# SW6124_A_B_C_LED.net
KiCad netlist of a schematic drawn in Altium Designer
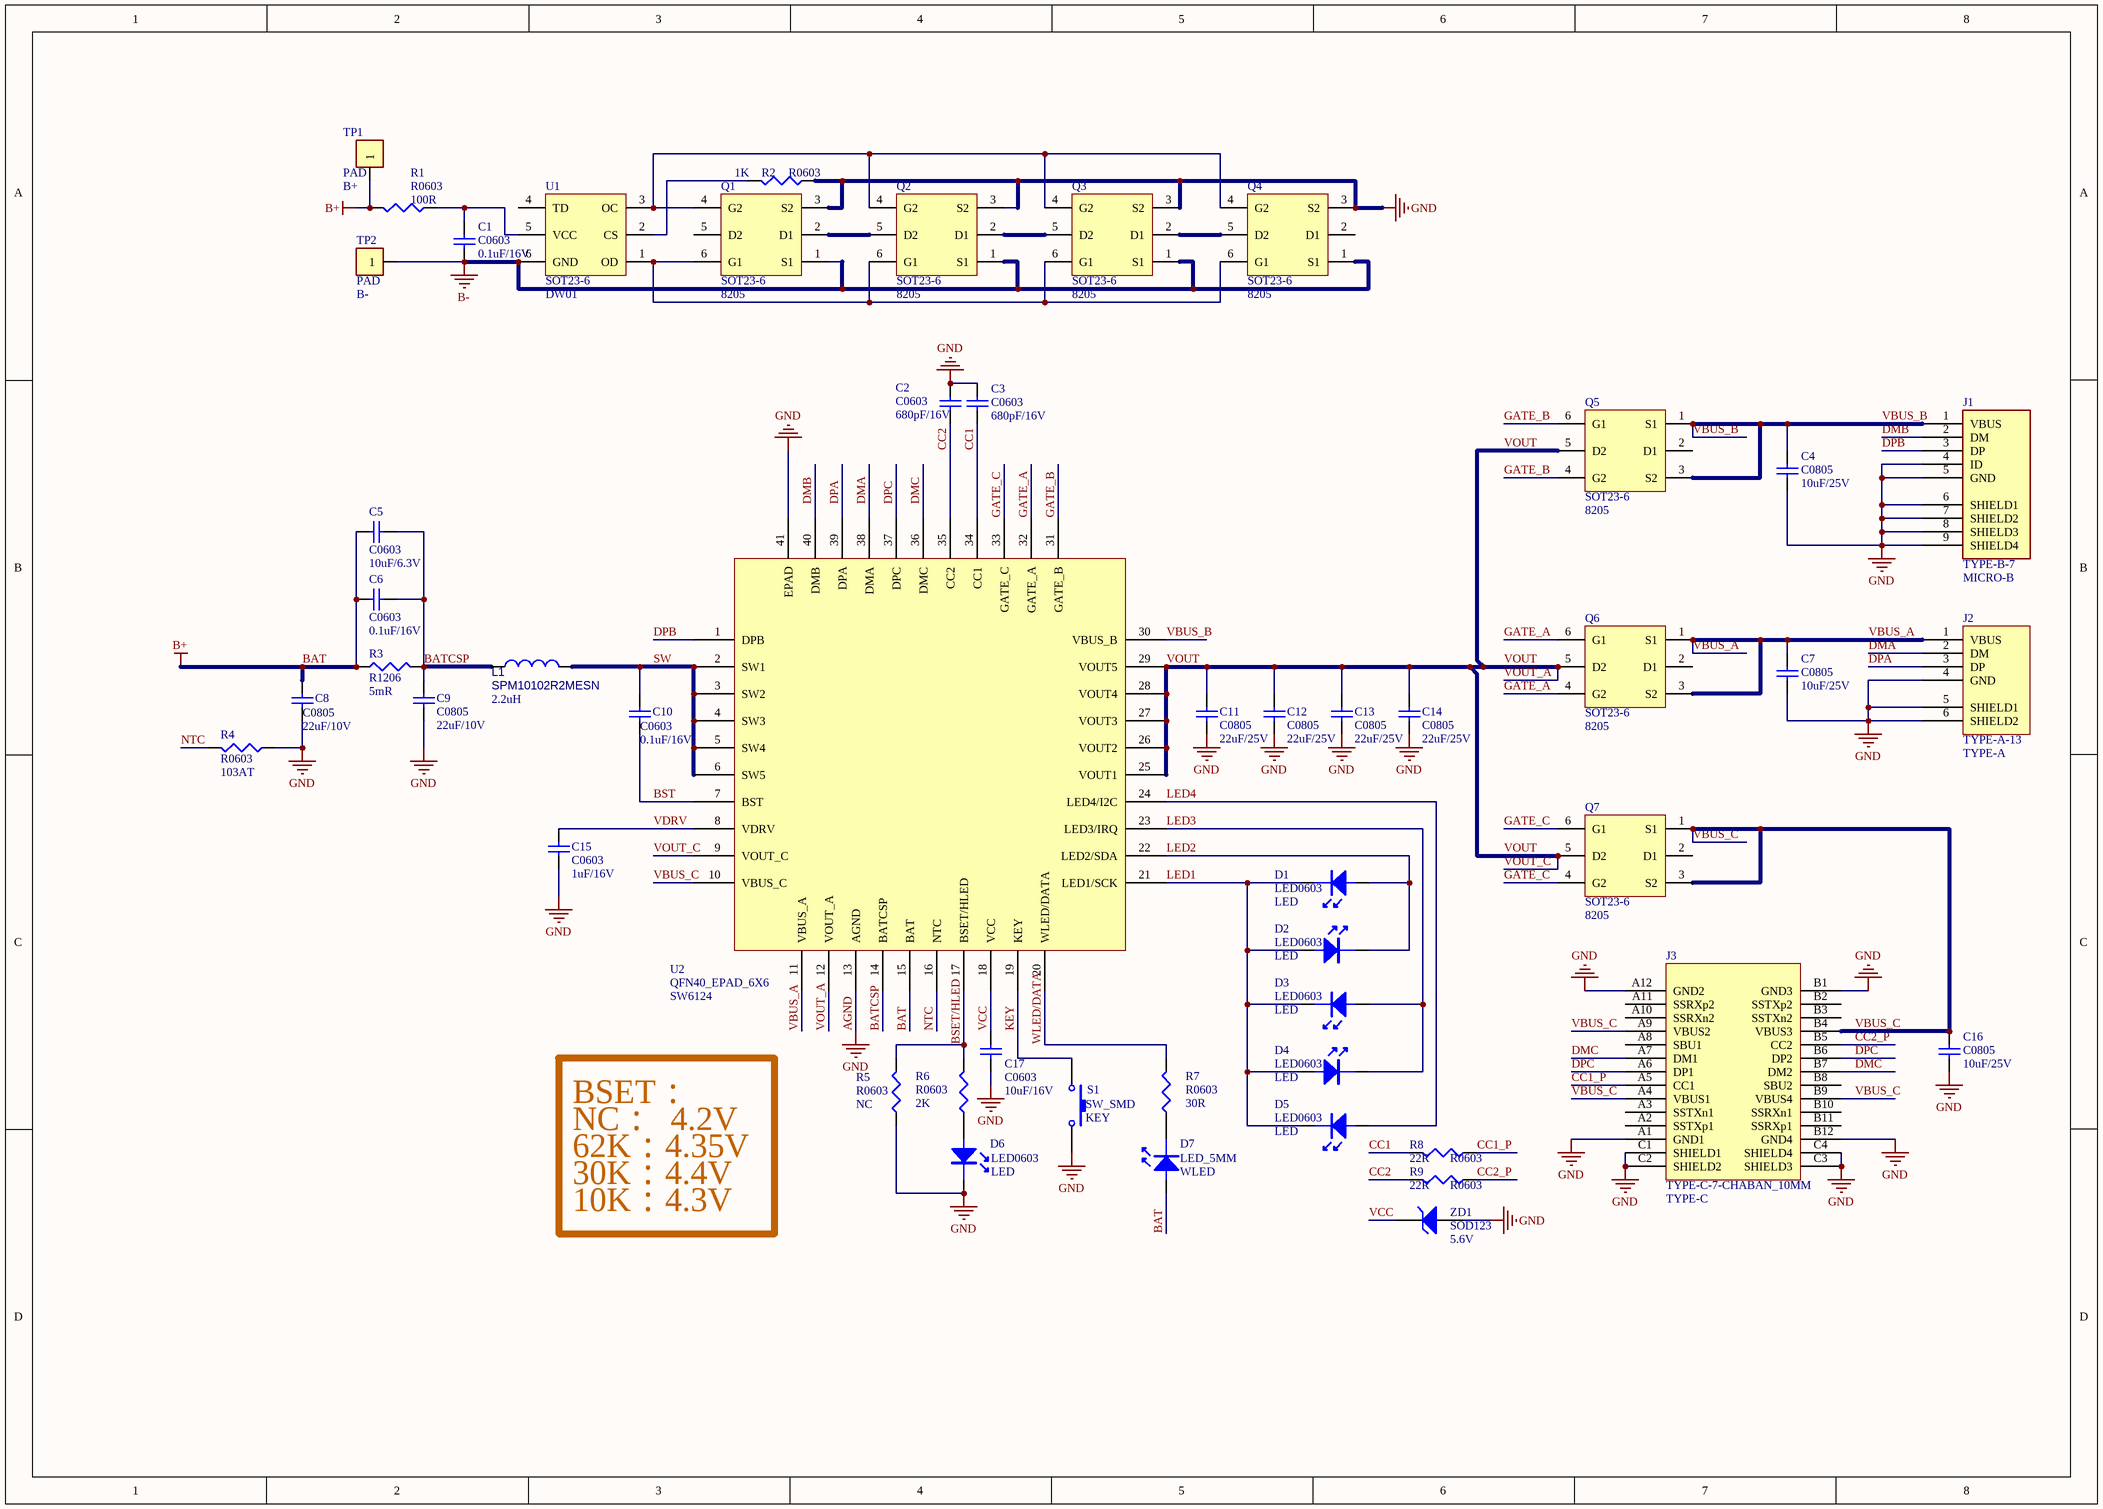
[diagram p0: SW6124+A+B+C+LED.SchDoc]

(export (version "E")
  (design (tool "Eeschema 10.0.6"))
  (components
    (comp (ref "C1")
      (value "C0603")
      (footprint "C0603")
      (description "Capacitor")
      (fields (field (name "ALTIUM_VALUE") "0.1uF/16V") (field (name "PUBLISHER") "Altium Limited"))
      (libsource (lib "*") (part "Cap"))
    )
    (comp (ref "C2")
      (value "C0603")
      (footprint "C0603")
      (description "Capacitor")
      (fields (field (name "ALTIUM_VALUE") "680pF/16V") (field (name "PUBLISHER") "Altium Limited"))
      (libsource (lib "*") (part "CAP0603"))
    )
    (comp (ref "C3")
      (value "C0603")
      (footprint "C0603")
      (description "Capacitor")
      (fields (field (name "ALTIUM_VALUE") "680pF/16V") (field (name "PUBLISHER") "Altium Limited"))
      (libsource (lib "*") (part "CAP0603"))
    )
    (comp (ref "C4")
      (value "C0805")
      (footprint "C0805")
      (description "Capacitor")
      (fields (field (name "ALTIUM_VALUE") "10uF/25V") (field (name "PUBLISHER") "Altium Limited"))
      (libsource (lib "*") (part "CAP0603"))
    )
    (comp (ref "C5")
      (value "C0603")
      (footprint "C0603")
      (description "Capacitor")
      (fields (field (name "ALTIUM_VALUE") "10uF/6.3V") (field (name "PUBLISHER") "Altium Limited"))
      (libsource (lib "*") (part "CAP0603"))
    )
    (comp (ref "C6")
      (value "C0603")
      (footprint "C0603")
      (description "Capacitor")
      (fields (field (name "ALTIUM_VALUE") "0.1uF/16V") (field (name "PUBLISHER") "Altium Limited"))
      (libsource (lib "*") (part "CAP0603"))
    )
    (comp (ref "C7")
      (value "C0805")
      (footprint "C0805")
      (description "Capacitor")
      (fields (field (name "ALTIUM_VALUE") "10uF/25V") (field (name "PUBLISHER") "Altium Limited"))
      (libsource (lib "*") (part "CAP0603"))
    )
    (comp (ref "C8")
      (value "C0805")
      (footprint "C0805")
      (description "Capacitor")
      (fields (field (name "ALTIUM_VALUE") "22uF/10V") (field (name "PUBLISHER") "Altium Limited"))
      (libsource (lib "*") (part "CAP0805"))
    )
    (comp (ref "C9")
      (value "C0805")
      (footprint "C0805")
      (description "Capacitor")
      (fields (field (name "ALTIUM_VALUE") "22uF/10V") (field (name "PUBLISHER") "Altium Limited"))
      (libsource (lib "*") (part "CAP0805"))
    )
    (comp (ref "C10")
      (value "C0603")
      (footprint "C0603")
      (description "Capacitor")
      (fields (field (name "ALTIUM_VALUE") "0.1uF/16V") (field (name "PUBLISHER") "Altium Limited"))
      (libsource (lib "*") (part "CAP0603"))
    )
    (comp (ref "C11")
      (value "C0805")
      (footprint "C0805")
      (description "Capacitor")
      (fields (field (name "ALTIUM_VALUE") "22uF/25V") (field (name "PUBLISHER") "Altium Limited"))
      (libsource (lib "*") (part "CAP0805"))
    )
    (comp (ref "C12")
      (value "C0805")
      (footprint "C0805")
      (description "Capacitor")
      (fields (field (name "ALTIUM_VALUE") "22uF/25V") (field (name "PUBLISHER") "Altium Limited"))
      (libsource (lib "*") (part "CAP0805"))
    )
    (comp (ref "C13")
      (value "C0805")
      (footprint "C0805")
      (description "Capacitor")
      (fields (field (name "ALTIUM_VALUE") "22uF/25V") (field (name "PUBLISHER") "Altium Limited"))
      (libsource (lib "*") (part "CAP0805"))
    )
    (comp (ref "C14")
      (value "C0805")
      (footprint "C0805")
      (description "Capacitor")
      (fields (field (name "ALTIUM_VALUE") "22uF/25V") (field (name "PUBLISHER") "Altium Limited"))
      (libsource (lib "*") (part "CAP0805"))
    )
    (comp (ref "C15")
      (value "C0603")
      (footprint "C0603")
      (description "Capacitor")
      (fields (field (name "ALTIUM_VALUE") "1uF/16V") (field (name "PUBLISHER") "Altium Limited"))
      (libsource (lib "*") (part "CAP0603"))
    )
    (comp (ref "C16")
      (value "C0805")
      (footprint "C0805")
      (description "Capacitor")
      (fields (field (name "ALTIUM_VALUE") "10uF/25V") (field (name "PUBLISHER") "Altium Limited"))
      (libsource (lib "*") (part "CAP0603"))
    )
    (comp (ref "C17")
      (value "C0603")
      (footprint "C0603")
      (description "Capacitor")
      (fields (field (name "ALTIUM_VALUE") "10uF/16V") (field (name "PUBLISHER") "Altium Limited"))
      (libsource (lib "*") (part "CAP0603"))
    )
    (comp (ref "D1") (value "LED") (footprint "LED0603") (libsource (lib "*") (part "LED")))
    (comp (ref "D2") (value "LED") (footprint "LED0603") (libsource (lib "*") (part "LED")))
    (comp (ref "D3") (value "LED") (footprint "LED0603") (libsource (lib "*") (part "LED")))
    (comp (ref "D4") (value "LED") (footprint "LED0603") (libsource (lib "*") (part "LED")))
    (comp (ref "D5") (value "LED") (footprint "LED0603") (libsource (lib "*") (part "LED")))
    (comp (ref "D6") (value "LED") (footprint "LED0603") (libsource (lib "*") (part "LED")))
    (comp (ref "D7")
      (value "WLED")
      (footprint "LED_5MM")
      (fields (field (name "FOOTPRINF") "LED_5MM") (field (name "Comment") "LED_5MM"))
      (libsource (lib "*") (part "LED"))
    )
    (comp (ref "J1")
      (value "MICRO-B")
      (footprint "TYPE-B-7")
      (fields (field (name "FOOTPRINTF") "TYPE-B-7") (field (name "Comment") "USB_MICRO_B"))
      (libsource (lib "*") (part "USB_MICRO_B"))
    )
    (comp (ref "J2")
      (value "TYPE-A")
      (footprint "TYPE-A-13")
      (fields (field (name "FOOTPRINF") "TYPE-A-13") (field (name "Comment") "TYPE-A-1"))
      (libsource (lib "*") (part "TYPE-A-1"))
    )
    (comp (ref "J3")
      (value "TYPE-C")
      (footprint "TYPE-C-7-CHABAN_10MM")
      (libsource (lib "*") (part "TYPE-C"))
    )
    (comp (ref "L1")
      (value "SPM10102R2MESN")
      (footprint "INDUCTOR_SPM1010")
      (fields (field (name "ALTIUM_VALUE") "2.2uH"))
      (libsource (lib "*") (part "INDUCTOR"))
    )
    (comp (ref "Q1")
      (value "8205")
      (footprint "SOT23-6")
      (fields (field (name "FOOTPRINF") "SOT23-6"))
      (libsource (lib "*") (part "8205B"))
    )
    (comp (ref "Q2")
      (value "8205")
      (footprint "SOT23-6")
      (fields (field (name "FOOTPRINF") "SOT23-6"))
      (libsource (lib "*") (part "8205B"))
    )
    (comp (ref "Q3")
      (value "8205")
      (footprint "SOT23-6")
      (fields (field (name "FOOTPRINF") "SOT23-6"))
      (libsource (lib "*") (part "8205B"))
    )
    (comp (ref "Q4")
      (value "8205")
      (footprint "SOT23-6")
      (fields (field (name "FOOTPRINF") "SOT23-6"))
      (libsource (lib "*") (part "8205B"))
    )
    (comp (ref "Q5")
      (value "8205")
      (footprint "SOT23-6")
      (fields (field (name "FOOTPRINF") "SOT23-6"))
      (libsource (lib "") (part "8205B_1"))
    )
    (comp (ref "Q6")
      (value "8205")
      (footprint "SOT23-6")
      (fields (field (name "FOOTPRINF") "SOT23-6"))
      (libsource (lib "") (part "8205B_1"))
    )
    (comp (ref "Q7")
      (value "8205")
      (footprint "SOT23-6")
      (fields (field (name "FOOTPRINF") "SOT23-6"))
      (libsource (lib "") (part "8205B_1"))
    )
    (comp (ref "R1")
      (value "R0603")
      (footprint "R0603")
      (description "Resistor")
      (fields (field (name "ALTIUM_VALUE") "100R") (field (name "PUBLISHER") "Altium Limited"))
      (libsource (lib "*") (part "Res3"))
    )
    (comp (ref "R2")
      (value "R0603")
      (footprint "R0603")
      (description "Resistor")
      (fields (field (name "ALTIUM_VALUE") "1K") (field (name "PUBLISHER") "Altium Limited"))
      (libsource (lib "*") (part "Res3"))
    )
    (comp (ref "R3")
      (value "R1206")
      (footprint "R1206")
      (description "Resistor")
      (fields (field (name "ALTIUM_VALUE") "5mR") (field (name "PUBLISHER") "Altium Limited"))
      (libsource (lib "*") (part "RES"))
    )
    (comp (ref "R4")
      (value "R0603")
      (footprint "R0603")
      (description "Resistor")
      (fields (field (name "ALTIUM_VALUE") "103AT") (field (name "PUBLISHER") "Altium Limited"))
      (libsource (lib "*") (part "RES"))
    )
    (comp (ref "R5")
      (value "R0603")
      (footprint "R0603")
      (description "Resistor")
      (fields (field (name "ALTIUM_VALUE") "NC") (field (name "PUBLISHER") "Altium Limited"))
      (libsource (lib "*") (part "RES"))
    )
    (comp (ref "R6")
      (value "R0603")
      (footprint "R0603")
      (description "Resistor")
      (fields (field (name "ALTIUM_VALUE") "2K") (field (name "PUBLISHER") "Altium Limited"))
      (libsource (lib "*") (part "RES"))
    )
    (comp (ref "R7")
      (value "R0603")
      (footprint "R0603")
      (description "Resistor")
      (fields (field (name "ALTIUM_VALUE") "30R") (field (name "PUBLISHER") "Altium Limited"))
      (libsource (lib "*") (part "RES"))
    )
    (comp (ref "R8")
      (value "R0603")
      (footprint "R0603")
      (description "Resistor")
      (fields (field (name "ALTIUM_VALUE") "22R") (field (name "PUBLISHER") "Altium Limited"))
      (libsource (lib "*") (part "RES"))
    )
    (comp (ref "R9")
      (value "R0603")
      (footprint "R0603")
      (description "Resistor")
      (fields (field (name "ALTIUM_VALUE") "22R") (field (name "PUBLISHER") "Altium Limited"))
      (libsource (lib "*") (part "RES"))
    )
    (comp (ref "S1")
      (value "KEY")
      (footprint "SW_SMD")
      (fields (field (name "FOOTPRINF") "SW_SMD"))
      (libsource (lib "*") (part "SW K"))
    )
    (comp (ref "TP1") (value "B+") (footprint "PAD") (libsource (lib "*") (part "Test Point")))
    (comp (ref "TP2") (value "B-") (footprint "PAD") (libsource (lib "") (part "Test Point_1")))
    (comp (ref "U1")
      (value "DW01")
      (footprint "SOT23-6")
      (fields (field (name "FOOTPRINF") "SOT23-6"))
      (libsource (lib "*") (part "DW01"))
    )
    (comp (ref "U2")
      (value "SW6124")
      (footprint "QFN40_EPAD_6X6")
      (libsource (lib "TEST") (part "SW6106_AFC"))
    )
    (comp (ref "ZD1")
      (value "SOD123")
      (footprint "SOD-123")
      (description "Zener Diode")
      (fields (field (name "ALTIUM_UNNAMED_1") "5.6V"))
      (libsource (lib "Miscellaneous Devices") (part "D Zener"))
    )
  )
  (nets
    (net (code "1") (name "/BATCSP") (class "Default")
      (node (ref "C5") (pin "2") (pinfunction "2_2") (pintype "passive"))
      (node (ref "C6") (pin "2") (pinfunction "2_2") (pintype "passive"))
      (node (ref "C9") (pin "2") (pinfunction "2_2") (pintype "passive"))
      (node (ref "L1") (pin "1") (pinfunction "1_1") (pintype "passive"))
      (node (ref "R3") (pin "2") (pinfunction "2_2") (pintype "passive"))
      (node (ref "U2") (pin "14") (pinfunction "BATCSP_14") (pintype "passive"))
    )
    (net (code "2") (name "/BSET{slash}HLED") (class "Default")
      (node (ref "R5") (pin "2") (pinfunction "2_2") (pintype "passive"))
      (node (ref "R6") (pin "2") (pinfunction "2_2") (pintype "passive"))
      (node (ref "U2") (pin "17") (pinfunction "BSET/HLED_17") (pintype "passive"))
    )
    (net (code "3") (name "/BST") (class "Default")
      (node (ref "C10") (pin "1") (pinfunction "1_1") (pintype "passive"))
      (node (ref "U2") (pin "7") (pinfunction "BST_7") (pintype "passive"))
    )
    (net (code "4") (name "/CC1") (class "Default")
      (node (ref "C3") (pin "1") (pinfunction "1_1") (pintype "passive"))
      (node (ref "R8") (pin "2") (pinfunction "2_2") (pintype "passive"))
      (node (ref "U2") (pin "34") (pinfunction "CC1_34") (pintype "passive"))
    )
    (net (code "5") (name "/CC1_P") (class "Default")
      (node (ref "J3") (pin "A5") (pinfunction "CC1_A5") (pintype "passive"))
      (node (ref "R8") (pin "1") (pinfunction "1_1") (pintype "passive"))
    )
    (net (code "6") (name "/CC2") (class "Default")
      (node (ref "C2") (pin "1") (pinfunction "1_1") (pintype "passive"))
      (node (ref "R9") (pin "2") (pinfunction "2_2") (pintype "passive"))
      (node (ref "U2") (pin "35") (pinfunction "CC2_35") (pintype "passive"))
    )
    (net (code "7") (name "/CC2_P") (class "Default")
      (node (ref "J3") (pin "B5") (pinfunction "CC2_B5") (pintype "passive"))
      (node (ref "R9") (pin "1") (pinfunction "1_1") (pintype "passive"))
    )
    (net (code "8") (name "/DMA") (class "Default")
      (node (ref "J2") (pin "2") (pinfunction "DM_2") (pintype "passive"))
      (node (ref "U2") (pin "38") (pinfunction "DMA_38") (pintype "passive"))
    )
    (net (code "9") (name "/DMB") (class "Default")
      (node (ref "J1") (pin "2") (pinfunction "DM_2") (pintype "passive"))
      (node (ref "U2") (pin "40") (pinfunction "DMB_40") (pintype "passive"))
    )
    (net (code "10") (name "/DMC") (class "Default")
      (node (ref "J3") (pin "A7") (pinfunction "DM1_A7") (pintype "passive"))
      (node (ref "J3") (pin "B7") (pinfunction "DM2_B7") (pintype "passive"))
      (node (ref "U2") (pin "36") (pinfunction "DMC_36") (pintype "passive"))
    )
    (net (code "11") (name "/DPA") (class "Default")
      (node (ref "J2") (pin "3") (pinfunction "DP_3") (pintype "passive"))
      (node (ref "U2") (pin "39") (pinfunction "DPA_39") (pintype "passive"))
    )
    (net (code "12") (name "/DPB") (class "Default")
      (node (ref "J1") (pin "3") (pinfunction "DP_3") (pintype "passive"))
      (node (ref "U2") (pin "1") (pinfunction "DPB_1") (pintype "passive"))
    )
    (net (code "13") (name "/DPC") (class "Default")
      (node (ref "J3") (pin "A6") (pinfunction "DP1_A6") (pintype "passive"))
      (node (ref "J3") (pin "B6") (pinfunction "DP2_B6") (pintype "passive"))
      (node (ref "U2") (pin "37") (pinfunction "DPC_37") (pintype "passive"))
    )
    (net (code "14") (name "/GATE_A") (class "Default")
      (node (ref "Q6") (pin "4") (pinfunction "G2_4") (pintype "passive"))
      (node (ref "Q6") (pin "6") (pinfunction "G1_6") (pintype "passive"))
      (node (ref "U2") (pin "32") (pinfunction "GATE_A_32") (pintype "passive"))
    )
    (net (code "15") (name "/GATE_B") (class "Default")
      (node (ref "Q5") (pin "4") (pinfunction "G2_4") (pintype "passive"))
      (node (ref "Q5") (pin "6") (pinfunction "G1_6") (pintype "passive"))
      (node (ref "U2") (pin "31") (pinfunction "GATE_B_31") (pintype "passive"))
    )
    (net (code "16") (name "/GATE_C") (class "Default")
      (node (ref "Q7") (pin "4") (pinfunction "G2_4") (pintype "passive"))
      (node (ref "Q7") (pin "6") (pinfunction "G1_6") (pintype "passive"))
      (node (ref "U2") (pin "33") (pinfunction "GATE_C_33") (pintype "passive"))
    )
    (net (code "17") (name "/KEY") (class "Default")
      (node (ref "S1") (pin "1") (pinfunction "1_1") (pintype "passive"))
      (node (ref "U2") (pin "19") (pinfunction "KEY_19") (pintype "passive"))
    )
    (net (code "18") (name "/LED1") (class "Default")
      (node (ref "D1") (pin "2") (pinfunction "K_2") (pintype "passive"))
      (node (ref "D2") (pin "1") (pinfunction "A_1") (pintype "passive"))
      (node (ref "D3") (pin "2") (pinfunction "K_2") (pintype "passive"))
      (node (ref "D4") (pin "1") (pinfunction "A_1") (pintype "passive"))
      (node (ref "D5") (pin "2") (pinfunction "K_2") (pintype "passive"))
      (node (ref "U2") (pin "21") (pinfunction "LED1/SCK_21") (pintype "passive"))
    )
    (net (code "19") (name "/LED2") (class "Default")
      (node (ref "D1") (pin "1") (pinfunction "A_1") (pintype "passive"))
      (node (ref "D2") (pin "2") (pinfunction "K_2") (pintype "passive"))
      (node (ref "U2") (pin "22") (pinfunction "LED2/SDA_22") (pintype "passive"))
    )
    (net (code "20") (name "/LED3") (class "Default")
      (node (ref "D3") (pin "1") (pinfunction "A_1") (pintype "passive"))
      (node (ref "D4") (pin "2") (pinfunction "K_2") (pintype "passive"))
      (node (ref "U2") (pin "23") (pinfunction "LED3/IRQ_23") (pintype "passive"))
    )
    (net (code "21") (name "/LED4") (class "Default")
      (node (ref "D5") (pin "1") (pinfunction "A_1") (pintype "passive"))
      (node (ref "U2") (pin "24") (pinfunction "LED4/I2C_24") (pintype "passive"))
    )
    (net (code "22") (name "/NTC") (class "Default")
      (node (ref "R4") (pin "2") (pinfunction "2_2") (pintype "passive"))
      (node (ref "U2") (pin "16") (pinfunction "NTC_16") (pintype "passive"))
    )
    (net (code "23") (name "/SW") (class "Default")
      (node (ref "C10") (pin "2") (pinfunction "2_2") (pintype "passive"))
      (node (ref "L1") (pin "2") (pinfunction "2_2") (pintype "passive"))
      (node (ref "U2") (pin "2") (pinfunction "SW1_2") (pintype "passive"))
      (node (ref "U2") (pin "3") (pinfunction "SW2_3") (pintype "passive"))
      (node (ref "U2") (pin "4") (pinfunction "SW3_4") (pintype "passive"))
      (node (ref "U2") (pin "5") (pinfunction "SW4_5") (pintype "passive"))
      (node (ref "U2") (pin "6") (pinfunction "SW5_6") (pintype "passive"))
    )
    (net (code "24") (name "/VBUS_A") (class "Default")
      (node (ref "C7") (pin "2") (pinfunction "2_2") (pintype "passive"))
      (node (ref "J2") (pin "1") (pinfunction "VBUS_1") (pintype "passive"))
      (node (ref "Q6") (pin "1") (pinfunction "S1_1") (pintype "passive"))
      (node (ref "Q6") (pin "3") (pinfunction "S2_3") (pintype "passive"))
      (node (ref "U2") (pin "11") (pinfunction "VBUS_A_11") (pintype "passive"))
    )
    (net (code "25") (name "/VBUS_B") (class "Default")
      (node (ref "C4") (pin "2") (pinfunction "2_2") (pintype "passive"))
      (node (ref "J1") (pin "1") (pinfunction "VBUS_1") (pintype "passive"))
      (node (ref "Q5") (pin "1") (pinfunction "S1_1") (pintype "passive"))
      (node (ref "Q5") (pin "3") (pinfunction "S2_3") (pintype "passive"))
      (node (ref "U2") (pin "30") (pinfunction "VBUS_B_30") (pintype "passive"))
    )
    (net (code "26") (name "/VBUS_C") (class "Default")
      (node (ref "C16") (pin "2") (pinfunction "2_2") (pintype "passive"))
      (node (ref "J3") (pin "A4") (pinfunction "VBUS1_A4") (pintype "passive"))
      (node (ref "J3") (pin "A9") (pinfunction "VBUS2_A9") (pintype "passive"))
      (node (ref "J3") (pin "B4") (pinfunction "VBUS3_B4") (pintype "passive"))
      (node (ref "J3") (pin "B9") (pinfunction "VBUS4_B9") (pintype "passive"))
      (node (ref "Q7") (pin "1") (pinfunction "S1_1") (pintype "passive"))
      (node (ref "Q7") (pin "3") (pinfunction "S2_3") (pintype "passive"))
      (node (ref "U2") (pin "10") (pinfunction "VBUS_C_10") (pintype "passive"))
    )
    (net (code "27") (name "/VCC") (class "Default")
      (node (ref "C17") (pin "2") (pinfunction "2_2") (pintype "passive"))
      (node (ref "U2") (pin "18") (pinfunction "VCC_18") (pintype "passive"))
      (node (ref "ZD1") (pin "2") (pinfunction "K_2") (pintype "passive"))
    )
    (net (code "28") (name "/VDRV") (class "Default")
      (node (ref "C15") (pin "2") (pinfunction "2_2") (pintype "passive"))
      (node (ref "U2") (pin "8") (pinfunction "VDRV_8") (pintype "passive"))
    )
    (net (code "29") (name "/VOUT") (class "Default")
      (node (ref "C11") (pin "2") (pinfunction "2_2") (pintype "passive"))
      (node (ref "C12") (pin "2") (pinfunction "2_2") (pintype "passive"))
      (node (ref "C13") (pin "2") (pinfunction "2_2") (pintype "passive"))
      (node (ref "C14") (pin "2") (pinfunction "2_2") (pintype "passive"))
      (node (ref "Q5") (pin "5") (pinfunction "D2_5") (pintype "passive"))
      (node (ref "Q6") (pin "5") (pinfunction "D2_5") (pintype "passive"))
      (node (ref "Q7") (pin "5") (pinfunction "D2_5") (pintype "passive"))
      (node (ref "U2") (pin "12") (pinfunction "VOUT_A_12") (pintype "passive"))
      (node (ref "U2") (pin "25") (pinfunction "VOUT1_25") (pintype "passive"))
      (node (ref "U2") (pin "26") (pinfunction "VOUT2_26") (pintype "passive"))
      (node (ref "U2") (pin "27") (pinfunction "VOUT3_27") (pintype "passive"))
      (node (ref "U2") (pin "28") (pinfunction "VOUT4_28") (pintype "passive"))
      (node (ref "U2") (pin "29") (pinfunction "VOUT5_29") (pintype "passive"))
      (node (ref "U2") (pin "9") (pinfunction "VOUT_C_9") (pintype "passive"))
    )
    (net (code "30") (name "/WLED{slash}DATA") (class "Default")
      (node (ref "R7") (pin "2") (pinfunction "2_2") (pintype "passive"))
      (node (ref "U2") (pin "20") (pinfunction "WLED/DATA_20") (pintype "passive"))
    )
    (net (code "31") (name "B+") (class "Default")
      (node (ref "C5") (pin "1") (pinfunction "1_1") (pintype "passive"))
      (node (ref "C6") (pin "1") (pinfunction "1_1") (pintype "passive"))
      (node (ref "C8") (pin "2") (pinfunction "2_2") (pintype "passive"))
      (node (ref "D7") (pin "1") (pinfunction "A_1") (pintype "passive"))
      (node (ref "R1") (pin "2") (pinfunction "2_2") (pintype "passive"))
      (node (ref "R3") (pin "1") (pinfunction "1_1") (pintype "passive"))
      (node (ref "TP1") (pin "1") (pinfunction "1_1") (pintype "passive"))
      (node (ref "U2") (pin "15") (pinfunction "BAT_15") (pintype "passive"))
    )
    (net (code "32") (name "B-") (class "Default")
      (node (ref "C1") (pin "1") (pinfunction "1_1") (pintype "passive"))
      (node (ref "Q1") (pin "1") (pinfunction "S1_1") (pintype "passive"))
      (node (ref "Q2") (pin "1") (pinfunction "S1_1") (pintype "passive"))
      (node (ref "Q3") (pin "1") (pinfunction "S1_1") (pintype "passive"))
      (node (ref "Q4") (pin "1") (pinfunction "S1_1") (pintype "passive"))
      (node (ref "TP2") (pin "1") (pinfunction "1_1") (pintype "passive"))
      (node (ref "U1") (pin "6") (pinfunction "GND_6") (pintype "passive"))
    )
    (net (code "33") (name "GND") (class "Default")
      (node (ref "C11") (pin "1") (pinfunction "1_1") (pintype "passive"))
      (node (ref "C12") (pin "1") (pinfunction "1_1") (pintype "passive"))
      (node (ref "C13") (pin "1") (pinfunction "1_1") (pintype "passive"))
      (node (ref "C14") (pin "1") (pinfunction "1_1") (pintype "passive"))
      (node (ref "C15") (pin "1") (pinfunction "1_1") (pintype "passive"))
      (node (ref "C16") (pin "1") (pinfunction "1_1") (pintype "passive"))
      (node (ref "C17") (pin "1") (pinfunction "1_1") (pintype "passive"))
      (node (ref "C2") (pin "2") (pinfunction "2_2") (pintype "passive"))
      (node (ref "C3") (pin "2") (pinfunction "2_2") (pintype "passive"))
      (node (ref "C4") (pin "1") (pinfunction "1_1") (pintype "passive"))
      (node (ref "C7") (pin "1") (pinfunction "1_1") (pintype "passive"))
      (node (ref "C8") (pin "1") (pinfunction "1_1") (pintype "passive"))
      (node (ref "C9") (pin "1") (pinfunction "1_1") (pintype "passive"))
      (node (ref "D6") (pin "2") (pinfunction "K_2") (pintype "passive"))
      (node (ref "J1") (pin "4") (pinfunction "ID_4") (pintype "passive"))
      (node (ref "J1") (pin "5") (pinfunction "GND_5") (pintype "passive"))
      (node (ref "J1") (pin "6") (pinfunction "SHIELD1_6") (pintype "passive"))
      (node (ref "J1") (pin "7") (pinfunction "SHIELD2_7") (pintype "passive"))
      (node (ref "J1") (pin "8") (pinfunction "SHIELD3_8") (pintype "passive"))
      (node (ref "J1") (pin "9") (pinfunction "SHIELD4_9") (pintype "passive"))
      (node (ref "J2") (pin "4") (pinfunction "GND_4") (pintype "passive"))
      (node (ref "J2") (pin "5") (pinfunction "SHIELD1_5") (pintype "passive"))
      (node (ref "J2") (pin "6") (pinfunction "SHIELD2_6") (pintype "passive"))
      (node (ref "J3") (pin "A1") (pinfunction "GND1_A1") (pintype "passive"))
      (node (ref "J3") (pin "A12") (pinfunction "GND2_A12") (pintype "passive"))
      (node (ref "J3") (pin "B1") (pinfunction "GND3_B1") (pintype "passive"))
      (node (ref "J3") (pin "B12") (pinfunction "GND4_B12") (pintype "passive"))
      (node (ref "J3") (pin "C1") (pinfunction "SHIELD1_C1") (pintype "passive"))
      (node (ref "J3") (pin "C2") (pinfunction "SHIELD2_C2") (pintype "passive"))
      (node (ref "J3") (pin "C3") (pinfunction "SHIELD3_C3") (pintype "passive"))
      (node (ref "J3") (pin "C4") (pinfunction "SHIELD4_C4") (pintype "passive"))
      (node (ref "Q1") (pin "3") (pinfunction "S2_3") (pintype "passive"))
      (node (ref "Q2") (pin "3") (pinfunction "S2_3") (pintype "passive"))
      (node (ref "Q3") (pin "3") (pinfunction "S2_3") (pintype "passive"))
      (node (ref "Q4") (pin "3") (pinfunction "S2_3") (pintype "passive"))
      (node (ref "R2") (pin "1") (pinfunction "1_1") (pintype "passive"))
      (node (ref "R4") (pin "1") (pinfunction "1_1") (pintype "passive"))
      (node (ref "R5") (pin "1") (pinfunction "1_1") (pintype "passive"))
      (node (ref "S1") (pin "2") (pinfunction "2_2") (pintype "passive"))
      (node (ref "U2") (pin "13") (pinfunction "AGND_13") (pintype "passive"))
      (node (ref "U2") (pin "41") (pinfunction "EPAD_41") (pintype "passive"))
      (node (ref "ZD1") (pin "1") (pinfunction "A_1") (pintype "passive"))
    )
    (net (code "34") (name "Net-(D6-A)") (class "Default")
      (node (ref "D6") (pin "1") (pinfunction "A_1") (pintype "passive"))
      (node (ref "R6") (pin "1") (pinfunction "1_1") (pintype "passive"))
    )
    (net (code "35") (name "Net-(D7-K)") (class "Default")
      (node (ref "D7") (pin "2") (pinfunction "K_2") (pintype "passive"))
      (node (ref "R7") (pin "1") (pinfunction "1_1") (pintype "passive"))
    )
    (net (code "36") (name "Net-(Q1-D1)") (class "Default")
      (node (ref "Q1") (pin "2") (pinfunction "D1_2") (pintype "passive"))
      (node (ref "Q2") (pin "5") (pinfunction "D2_5") (pintype "passive"))
    )
    (net (code "37") (name "Net-(Q1-G1)") (class "Default")
      (node (ref "Q1") (pin "6") (pinfunction "G1_6") (pintype "passive"))
      (node (ref "Q2") (pin "6") (pinfunction "G1_6") (pintype "passive"))
      (node (ref "Q3") (pin "6") (pinfunction "G1_6") (pintype "passive"))
      (node (ref "Q4") (pin "6") (pinfunction "G1_6") (pintype "passive"))
      (node (ref "U1") (pin "1") (pinfunction "OD_1") (pintype "passive"))
    )
    (net (code "38") (name "Net-(Q1-G2)") (class "Default")
      (node (ref "Q1") (pin "4") (pinfunction "G2_4") (pintype "passive"))
      (node (ref "Q2") (pin "4") (pinfunction "G2_4") (pintype "passive"))
      (node (ref "Q3") (pin "4") (pinfunction "G2_4") (pintype "passive"))
      (node (ref "Q4") (pin "4") (pinfunction "G2_4") (pintype "passive"))
      (node (ref "U1") (pin "3") (pinfunction "OC_3") (pintype "passive"))
    )
    (net (code "39") (name "Net-(Q2-D1)") (class "Default")
      (node (ref "Q2") (pin "2") (pinfunction "D1_2") (pintype "passive"))
      (node (ref "Q3") (pin "5") (pinfunction "D2_5") (pintype "passive"))
    )
    (net (code "40") (name "Net-(Q3-D1)") (class "Default")
      (node (ref "Q3") (pin "2") (pinfunction "D1_2") (pintype "passive"))
      (node (ref "Q4") (pin "5") (pinfunction "D2_5") (pintype "passive"))
    )
    (net (code "41") (name "Net-(U1-CS)") (class "Default")
      (node (ref "R2") (pin "2") (pinfunction "2_2") (pintype "passive"))
      (node (ref "U1") (pin "2") (pinfunction "CS_2") (pintype "passive"))
    )
    (net (code "42") (name "Net-(U1-VCC)") (class "Default")
      (node (ref "C1") (pin "2") (pinfunction "2_2") (pintype "passive"))
      (node (ref "R1") (pin "1") (pinfunction "1_1") (pintype "passive"))
      (node (ref "U1") (pin "5") (pinfunction "VCC_5") (pintype "passive"))
    )
    (net (code "43") (name "unconnected-(J3-SBU1-PadA8)") (class "Default")
      (node (ref "J3") (pin "A8") (pinfunction "SBU1_A8") (pintype "passive"))
    )
    (net (code "44") (name "unconnected-(J3-SBU2-PadB8)") (class "Default")
      (node (ref "J3") (pin "B8") (pinfunction "SBU2_B8") (pintype "passive"))
    )
    (net (code "45") (name "unconnected-(J3-SSRXn1-PadB10)") (class "Default")
      (node (ref "J3") (pin "B10") (pinfunction "SSRXn1_B10") (pintype "passive"))
    )
    (net (code "46") (name "unconnected-(J3-SSRXn2-PadA10)") (class "Default")
      (node (ref "J3") (pin "A10") (pinfunction "SSRXn2_A10") (pintype "passive"))
    )
    (net (code "47") (name "unconnected-(J3-SSRXp1-PadB11)") (class "Default")
      (node (ref "J3") (pin "B11") (pinfunction "SSRXp1_B11") (pintype "passive"))
    )
    (net (code "48") (name "unconnected-(J3-SSRXp2-PadA11)") (class "Default")
      (node (ref "J3") (pin "A11") (pinfunction "SSRXp2_A11") (pintype "passive"))
    )
    (net (code "49") (name "unconnected-(J3-SSTXn1-PadA3)") (class "Default")
      (node (ref "J3") (pin "A3") (pinfunction "SSTXn1_A3") (pintype "passive"))
    )
    (net (code "50") (name "unconnected-(J3-SSTXn2-PadB3)") (class "Default")
      (node (ref "J3") (pin "B3") (pinfunction "SSTXn2_B3") (pintype "passive"))
    )
    (net (code "51") (name "unconnected-(J3-SSTXp1-PadA2)") (class "Default")
      (node (ref "J3") (pin "A2") (pinfunction "SSTXp1_A2") (pintype "passive"))
    )
    (net (code "52") (name "unconnected-(J3-SSTXp2-PadB2)") (class "Default")
      (node (ref "J3") (pin "B2") (pinfunction "SSTXp2_B2") (pintype "passive"))
    )
    (net (code "53") (name "unconnected-(Q1-D2-Pad5)") (class "Default")
      (node (ref "Q1") (pin "5") (pinfunction "D2_5") (pintype "passive"))
    )
    (net (code "54") (name "unconnected-(Q4-D1-Pad2)") (class "Default")
      (node (ref "Q4") (pin "2") (pinfunction "D1_2") (pintype "passive"))
    )
    (net (code "55") (name "unconnected-(Q5-D1-Pad2)") (class "Default")
      (node (ref "Q5") (pin "2") (pinfunction "D1_2") (pintype "passive"))
    )
    (net (code "56") (name "unconnected-(Q6-D1-Pad2)") (class "Default")
      (node (ref "Q6") (pin "2") (pinfunction "D1_2") (pintype "passive"))
    )
    (net (code "57") (name "unconnected-(Q7-D1-Pad2)") (class "Default")
      (node (ref "Q7") (pin "2") (pinfunction "D1_2") (pintype "passive"))
    )
    (net (code "58") (name "unconnected-(U1-TD-Pad4)") (class "Default")
      (node (ref "U1") (pin "4") (pinfunction "TD_4") (pintype "passive"))
    )
  )
)
